# motors_motherBoard_simple.net
KiCad netlist of a schematic drawn in EAGLE
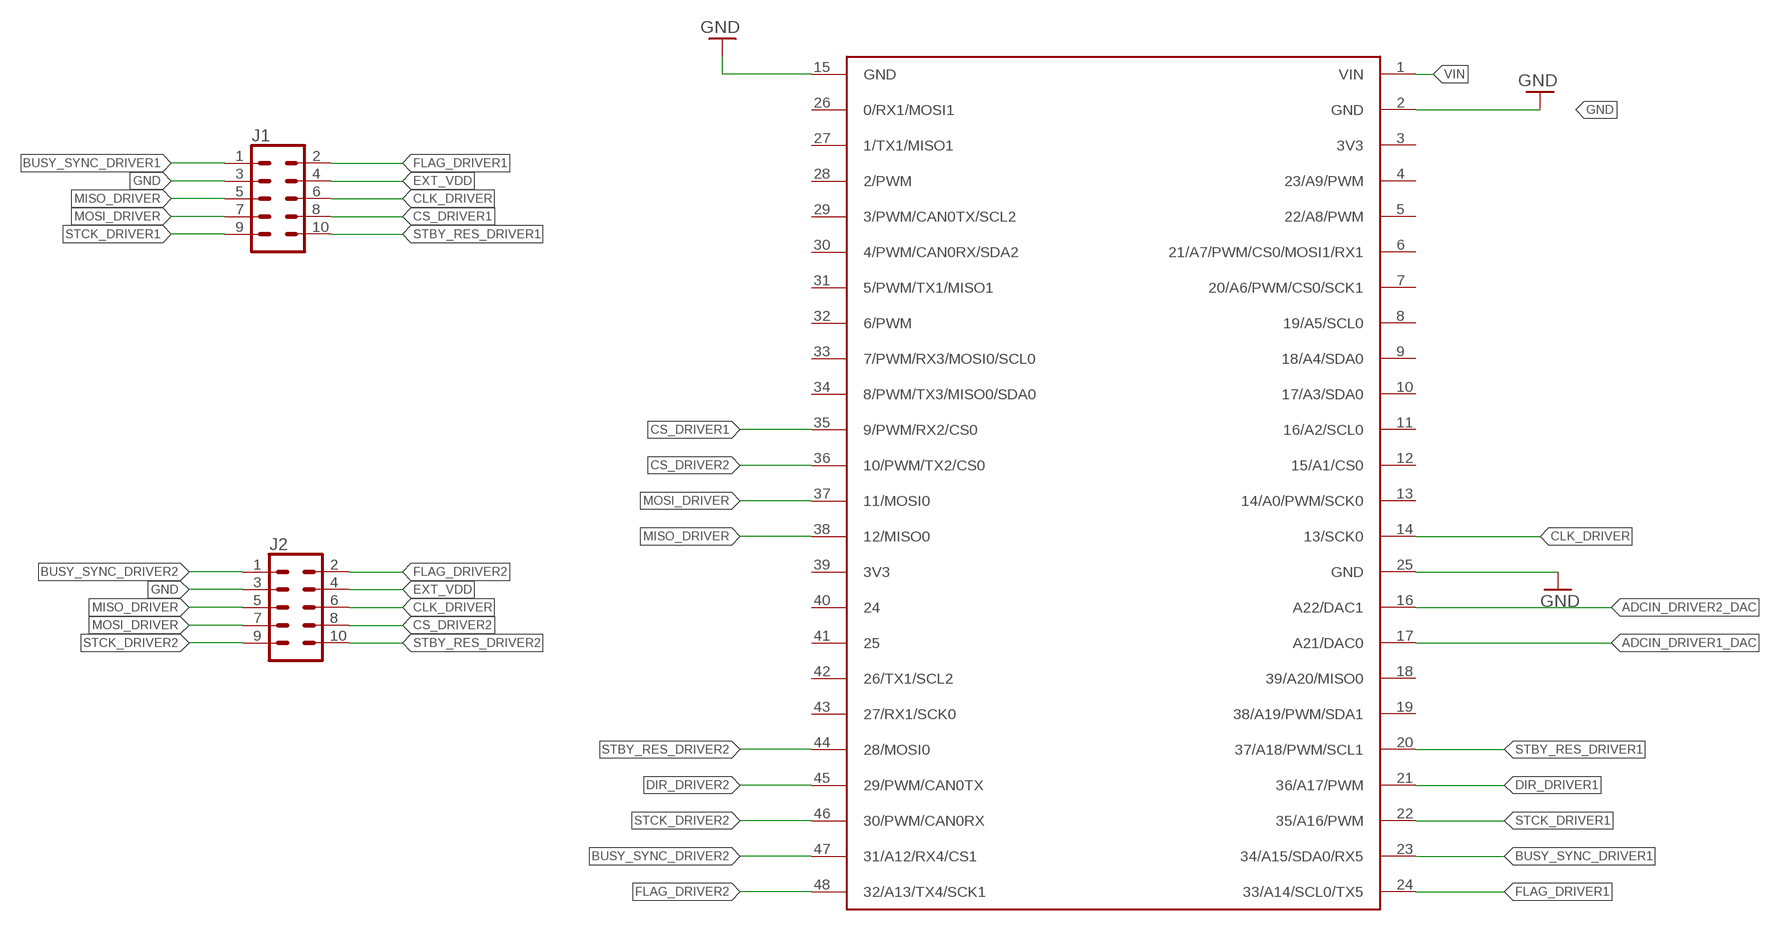
[diagram p0: schematic, sheet 1]

(export (version "E")
  (design (tool "Eeschema 10.0.6"))
  (components
    (comp (ref "J1")
      (value "CONN_05X2SHD_LOCK")
      (footprint "eagle-import:2X5-SHROUDED_LOCK")
      (libsource (lib "eagle-import") (part "CONN_05X2SHD_LOCK"))
    )
    (comp (ref "J2")
      (value "CONN_05X2SHD_LOCK")
      (footprint "eagle-import:2X5-SHROUDED_LOCK")
      (libsource (lib "eagle-import") (part "CONN_05X2SHD_LOCK"))
    )
    (comp (ref "U$3")
      (value "TEENSY_BASE_ADAPTER")
      (footprint "eagle-import:TEENSY_BASE_ADAPTER")
      (libsource (lib "eagle-import") (part "TEENSY_BASE_ADAPTER"))
    )
  )
  (nets
    (net (code "1") (name "ADCIN_DRIVER1_DAC") (class "Default")
      (node (ref "U$3") (pin "17") (pinfunction "A21/DAC0_17") (pintype "bidirectional"))
    )
    (net (code "2") (name "ADCIN_DRIVER2_DAC") (class "Default")
      (node (ref "U$3") (pin "16") (pinfunction "A22/DAC1_16") (pintype "bidirectional"))
    )
    (net (code "3") (name "BUSY_SYNC_DRIVER1") (class "Default")
      (node (ref "J1") (pin "1") (pinfunction "1_1") (pintype "passive"))
      (node (ref "U$3") (pin "23") (pinfunction "34/A15/SDA0/RX5_23") (pintype "bidirectional"))
    )
    (net (code "4") (name "BUSY_SYNC_DRIVER2") (class "Default")
      (node (ref "J2") (pin "1") (pinfunction "1_1") (pintype "passive"))
      (node (ref "U$3") (pin "47") (pinfunction "31/A12/RX4/CS1_47") (pintype "bidirectional"))
    )
    (net (code "5") (name "CLK_DRIVER") (class "Default")
      (node (ref "J1") (pin "6") (pinfunction "6_6") (pintype "passive"))
      (node (ref "J2") (pin "6") (pinfunction "6_6") (pintype "passive"))
      (node (ref "U$3") (pin "14") (pinfunction "13/SCK0_14") (pintype "bidirectional"))
    )
    (net (code "6") (name "CS_DRIVER1") (class "Default")
      (node (ref "J1") (pin "8") (pinfunction "8_8") (pintype "passive"))
      (node (ref "U$3") (pin "35") (pinfunction "9/PWM/RX2/CS0_35") (pintype "bidirectional"))
    )
    (net (code "7") (name "CS_DRIVER2") (class "Default")
      (node (ref "J2") (pin "8") (pinfunction "8_8") (pintype "passive"))
      (node (ref "U$3") (pin "36") (pinfunction "10/PWM/TX2/CS0_36") (pintype "bidirectional"))
    )
    (net (code "8") (name "DIR_DRIVER1") (class "Default")
      (node (ref "U$3") (pin "21") (pinfunction "36/A17/PWM_21") (pintype "bidirectional"))
    )
    (net (code "9") (name "DIR_DRIVER2") (class "Default")
      (node (ref "U$3") (pin "45") (pinfunction "29/PWM/CAN0TX_45") (pintype "bidirectional"))
    )
    (net (code "10") (name "EXT_VDD") (class "Default")
      (node (ref "J1") (pin "4") (pinfunction "4_4") (pintype "passive"))
      (node (ref "J2") (pin "4") (pinfunction "4_4") (pintype "passive"))
    )
    (net (code "11") (name "FLAG_DRIVER1") (class "Default")
      (node (ref "J1") (pin "2") (pinfunction "2_2") (pintype "passive"))
      (node (ref "U$3") (pin "24") (pinfunction "33/A14/SCL0/TX5_24") (pintype "bidirectional"))
    )
    (net (code "12") (name "FLAG_DRIVER2") (class "Default")
      (node (ref "J2") (pin "2") (pinfunction "2_2") (pintype "passive"))
      (node (ref "U$3") (pin "48") (pinfunction "32/A13/TX4/SCK1_48") (pintype "bidirectional"))
    )
    (net (code "13") (name "GND") (class "Default")
      (node (ref "J1") (pin "3") (pinfunction "3_3") (pintype "passive"))
      (node (ref "J2") (pin "3") (pinfunction "3_3") (pintype "passive"))
      (node (ref "U$3") (pin "15") (pinfunction "GND_15") (pintype "bidirectional"))
      (node (ref "U$3") (pin "2") (pinfunction "GND_2") (pintype "bidirectional"))
      (node (ref "U$3") (pin "25") (pinfunction "GND_25") (pintype "bidirectional"))
    )
    (net (code "14") (name "MISO_DRIVER") (class "Default")
      (node (ref "J1") (pin "5") (pinfunction "5_5") (pintype "passive"))
      (node (ref "J2") (pin "5") (pinfunction "5_5") (pintype "passive"))
      (node (ref "U$3") (pin "38") (pinfunction "12/MISO0_38") (pintype "bidirectional"))
    )
    (net (code "15") (name "MOSI_DRIVER") (class "Default")
      (node (ref "J1") (pin "7") (pinfunction "7_7") (pintype "passive"))
      (node (ref "J2") (pin "7") (pinfunction "7_7") (pintype "passive"))
      (node (ref "U$3") (pin "37") (pinfunction "11/MOSI0_37") (pintype "bidirectional"))
    )
    (net (code "16") (name "STBY_RES_DRIVER1") (class "Default")
      (node (ref "J1") (pin "10") (pinfunction "10_10") (pintype "passive"))
      (node (ref "U$3") (pin "20") (pinfunction "37/A18/PWM/SCL1_20") (pintype "bidirectional"))
    )
    (net (code "17") (name "STBY_RES_DRIVER2") (class "Default")
      (node (ref "J2") (pin "10") (pinfunction "10_10") (pintype "passive"))
      (node (ref "U$3") (pin "44") (pinfunction "28/MOSI0_44") (pintype "bidirectional"))
    )
    (net (code "18") (name "STCK_DRIVER1") (class "Default")
      (node (ref "J1") (pin "9") (pinfunction "9_9") (pintype "passive"))
      (node (ref "U$3") (pin "22") (pinfunction "35/A16/PWM_22") (pintype "bidirectional"))
    )
    (net (code "19") (name "STCK_DRIVER2") (class "Default")
      (node (ref "J2") (pin "9") (pinfunction "9_9") (pintype "passive"))
      (node (ref "U$3") (pin "46") (pinfunction "30/PWM/CAN0RX_46") (pintype "bidirectional"))
    )
    (net (code "20") (name "VIN") (class "Default")
      (node (ref "U$3") (pin "1") (pinfunction "VIN_1") (pintype "bidirectional"))
    )
    (net (code "21") (name "unconnected-(U$3-0{slash}RX1{slash}MOSI1-Pad26)") (class "Default")
      (node (ref "U$3") (pin "26") (pinfunction "0/RX1/MOSI1_26") (pintype "bidirectional"))
    )
    (net (code "22") (name "unconnected-(U$3-1{slash}TX1{slash}MISO1-Pad27)") (class "Default")
      (node (ref "U$3") (pin "27") (pinfunction "1/TX1/MISO1_27") (pintype "bidirectional"))
    )
    (net (code "23") (name "unconnected-(U$3-2{slash}PWM-Pad28)") (class "Default")
      (node (ref "U$3") (pin "28") (pinfunction "2/PWM_28") (pintype "bidirectional"))
    )
    (net (code "24") (name "unconnected-(U$3-3V3-Pad3)") (class "Default")
      (node (ref "U$3") (pin "3") (pinfunction "3V3_3") (pintype "bidirectional"))
    )
    (net (code "25") (name "unconnected-(U$3-3V3-Pad39)") (class "Default")
      (node (ref "U$3") (pin "39") (pinfunction "3V3_39") (pintype "bidirectional"))
    )
    (net (code "26") (name "unconnected-(U$3-3{slash}PWM{slash}CAN0TX{slash}SCL2-Pad29)") (class "Default")
      (node (ref "U$3") (pin "29") (pinfunction "3/PWM/CAN0TX/SCL2_29") (pintype "bidirectional"))
    )
    (net (code "27") (name "unconnected-(U$3-4{slash}PWM{slash}CAN0RX{slash}SDA2-Pad30)") (class "Default")
      (node (ref "U$3") (pin "30") (pinfunction "4/PWM/CAN0RX/SDA2_30") (pintype "bidirectional"))
    )
    (net (code "28") (name "unconnected-(U$3-5{slash}PWM{slash}TX1{slash}MISO1-Pad31)") (class "Default")
      (node (ref "U$3") (pin "31") (pinfunction "5/PWM/TX1/MISO1_31") (pintype "bidirectional"))
    )
    (net (code "29") (name "unconnected-(U$3-6{slash}PWM-Pad32)") (class "Default")
      (node (ref "U$3") (pin "32") (pinfunction "6/PWM_32") (pintype "bidirectional"))
    )
    (net (code "30") (name "unconnected-(U$3-7{slash}PWM{slash}RX3{slash}MOSI0{slash}SCL0-Pad33)") (class "Default")
      (node (ref "U$3") (pin "33") (pinfunction "7/PWM/RX3/MOSI0/SCL0_33") (pintype "bidirectional"))
    )
    (net (code "31") (name "unconnected-(U$3-8{slash}PWM{slash}TX3{slash}MISO0{slash}SDA0-Pad34)") (class "Default")
      (node (ref "U$3") (pin "34") (pinfunction "8/PWM/TX3/MISO0/SDA0_34") (pintype "bidirectional"))
    )
    (net (code "32") (name "unconnected-(U$3-14{slash}A0{slash}PWM{slash}SCK0-Pad13)") (class "Default")
      (node (ref "U$3") (pin "13") (pinfunction "14/A0/PWM/SCK0_13") (pintype "bidirectional"))
    )
    (net (code "33") (name "unconnected-(U$3-15{slash}A1{slash}CS0-Pad12)") (class "Default")
      (node (ref "U$3") (pin "12") (pinfunction "15/A1/CS0_12") (pintype "bidirectional"))
    )
    (net (code "34") (name "unconnected-(U$3-16{slash}A2{slash}SCL0-Pad11)") (class "Default")
      (node (ref "U$3") (pin "11") (pinfunction "16/A2/SCL0_11") (pintype "bidirectional"))
    )
    (net (code "35") (name "unconnected-(U$3-17{slash}A3{slash}SDA0-Pad10)") (class "Default")
      (node (ref "U$3") (pin "10") (pinfunction "17/A3/SDA0_10") (pintype "bidirectional"))
    )
    (net (code "36") (name "unconnected-(U$3-18{slash}A4{slash}SDA0-Pad9)") (class "Default")
      (node (ref "U$3") (pin "9") (pinfunction "18/A4/SDA0_9") (pintype "bidirectional"))
    )
    (net (code "37") (name "unconnected-(U$3-19{slash}A5{slash}SCL0-Pad8)") (class "Default")
      (node (ref "U$3") (pin "8") (pinfunction "19/A5/SCL0_8") (pintype "bidirectional"))
    )
    (net (code "38") (name "unconnected-(U$3-20{slash}A6{slash}PWM{slash}CS0{slash}SCK1-Pad7)") (class "Default")
      (node (ref "U$3") (pin "7") (pinfunction "20/A6/PWM/CS0/SCK1_7") (pintype "bidirectional"))
    )
    (net (code "39") (name "unconnected-(U$3-21{slash}A7{slash}PWM{slash}CS0{slash}MOSI1{slash}RX1-Pad6)") (class "Default")
      (node (ref "U$3") (pin "6") (pinfunction "21/A7/PWM/CS0/MOSI1/RX1_6") (pintype "bidirectional"))
    )
    (net (code "40") (name "unconnected-(U$3-22{slash}A8{slash}PWM-Pad5)") (class "Default")
      (node (ref "U$3") (pin "5") (pinfunction "22/A8/PWM_5") (pintype "bidirectional"))
    )
    (net (code "41") (name "unconnected-(U$3-23{slash}A9{slash}PWM-Pad4)") (class "Default")
      (node (ref "U$3") (pin "4") (pinfunction "23/A9/PWM_4") (pintype "bidirectional"))
    )
    (net (code "42") (name "unconnected-(U$3-24-Pad40)") (class "Default")
      (node (ref "U$3") (pin "40") (pinfunction "24_40") (pintype "bidirectional"))
    )
    (net (code "43") (name "unconnected-(U$3-25-Pad41)") (class "Default")
      (node (ref "U$3") (pin "41") (pinfunction "25_41") (pintype "bidirectional"))
    )
    (net (code "44") (name "unconnected-(U$3-26{slash}TX1{slash}SCL2-Pad42)") (class "Default")
      (node (ref "U$3") (pin "42") (pinfunction "26/TX1/SCL2_42") (pintype "bidirectional"))
    )
    (net (code "45") (name "unconnected-(U$3-27{slash}RX1{slash}SCK0-Pad43)") (class "Default")
      (node (ref "U$3") (pin "43") (pinfunction "27/RX1/SCK0_43") (pintype "bidirectional"))
    )
    (net (code "46") (name "unconnected-(U$3-38{slash}A19{slash}PWM{slash}SDA1-Pad19)") (class "Default")
      (node (ref "U$3") (pin "19") (pinfunction "38/A19/PWM/SDA1_19") (pintype "bidirectional"))
    )
    (net (code "47") (name "unconnected-(U$3-39{slash}A20{slash}MISO0-Pad18)") (class "Default")
      (node (ref "U$3") (pin "18") (pinfunction "39/A20/MISO0_18") (pintype "bidirectional"))
    )
  )
)
